# SAME51_PINOUT.net
KiCad netlist of a schematic drawn in Altium Designer
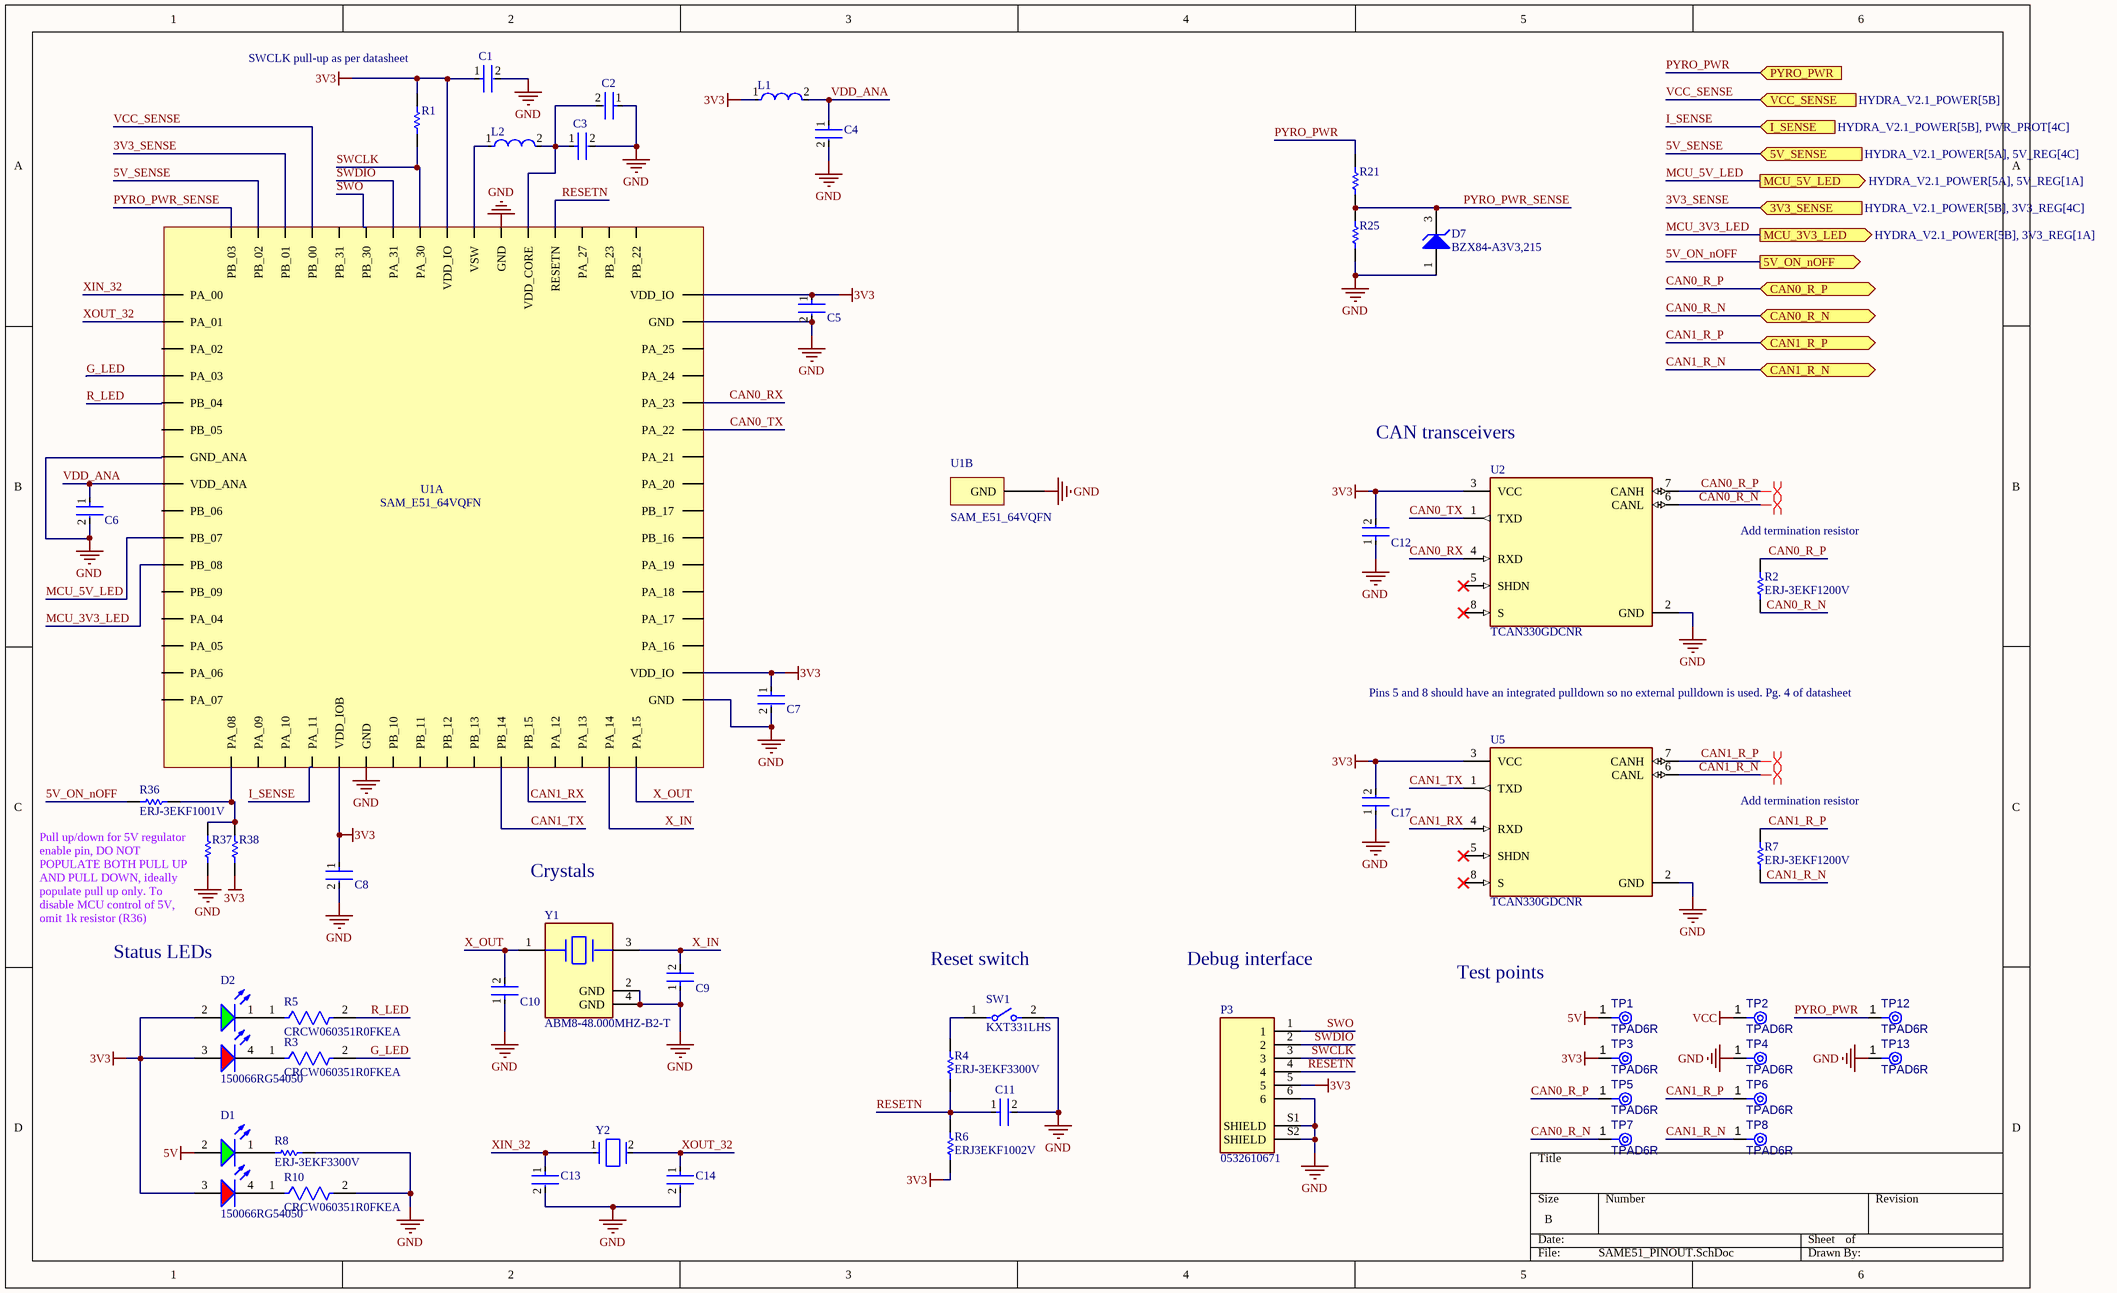
[diagram p0: SAME51_PINOUT.SchDoc]

(export (version "E")
  (design (tool "Eeschema 10.0.6"))
  (components
    (comp (ref "C1")
      (value "C0402C104K8PACTU")
      (footprint "FP-C0402-BB-MFG")
      (description "CAP CER 0.1UF 10V X5R 0402")
      (fields (field (name "MANUFACTURER") "Kemet") (field (name "TOLERANCE") "0.1"))
      (libsource (lib "Altium Content Vault") (part "b4654b650e69147ec39a6b967a45e02"))
    )
    (comp (ref "C2")
      (value "GRM155R60J475ME47D")
      (footprint "FP-GRM155-0_1-IPC_B")
      (description "Chip Multilayer Ceramic Capacitors for General Purpose, 0402, 4.7uF, X5R, 15%, 20%, 6.3V")
      (fields (field (name "VOLTAGE") "6.3V") (field (name "TOLERANCE") "20%"))
      (libsource (lib "Altium Content Vault") (part "11868f565c42a9108669ba33697ecf6"))
    )
    (comp (ref "C3")
      (value "C0402C104K8PACTU")
      (footprint "FP-C0402-BB-MFG")
      (description "CAP CER 0.1UF 10V X5R 0402")
      (fields (field (name "MANUFACTURER") "Kemet") (field (name "TOLERANCE") "0.1"))
      (libsource (lib "Altium Content Vault") (part "b4654b650e69147ec39a6b967a45e02"))
    )
    (comp (ref "C4")
      (value "C0805C106K8PACTU")
      (footprint "FP-C0805C-DG-MFG")
      (description "CAP CER 10UF 10V X5R 0805")
      (fields (field (name "TOLERANCE") "10%") (field (name "MANUFACTURER") "Kemet"))
      (libsource (lib "Altium Content Vault") (part "11868f565c42a9108669ba33697ecf6"))
    )
    (comp (ref "C5")
      (value "C0402C104K8PACTU")
      (footprint "FP-C0402-BB-MFG")
      (description "CAP CER 0.1UF 10V X5R 0402")
      (fields (field (name "MANUFACTURER") "Kemet") (field (name "TOLERANCE") "0.1"))
      (libsource (lib "Altium Content Vault") (part "b4654b650e69147ec39a6b967a45e02"))
    )
    (comp (ref "C6")
      (value "C0402C104K8PACTU")
      (footprint "FP-C0402-BB-MFG")
      (description "CAP CER 0.1UF 10V X5R 0402")
      (fields (field (name "MANUFACTURER") "Kemet") (field (name "TOLERANCE") "0.1"))
      (libsource (lib "Altium Content Vault") (part "b4654b650e69147ec39a6b967a45e02"))
    )
    (comp (ref "C7")
      (value "C0402C104K8PACTU")
      (footprint "FP-C0402-BB-MFG")
      (description "CAP CER 0.1UF 10V X5R 0402")
      (fields (field (name "MANUFACTURER") "Kemet") (field (name "TOLERANCE") "0.1"))
      (libsource (lib "Altium Content Vault") (part "b4654b650e69147ec39a6b967a45e02"))
    )
    (comp (ref "C8")
      (value "C0402C104K8PACTU")
      (footprint "FP-C0402-BB-MFG")
      (description "CAP CER 0.1UF 10V X5R 0402")
      (fields (field (name "MANUFACTURER") "Kemet") (field (name "TOLERANCE") "0.1"))
      (libsource (lib "Altium Content Vault") (part "b4654b650e69147ec39a6b967a45e02"))
    )
    (comp (ref "C9")
      (value "08051A6R8CAT2A")
      (footprint "FP-0805-L_2_01_0_2-W_1_25-MFG")
      (description "General Purpose Ceramic Capacitor, 0805, 6.8pF, 0.25pF, C0G, 30ppm/°C, 100V")
      (fields (field (name "VOLTAGE") "100V") (field (name "TOLERANCE") "5%"))
      (libsource (lib "Altium Content Vault") (part "02cd4be3c70576c341d710602a673aa"))
    )
    (comp (ref "C10")
      (value "08051A6R8CAT2A")
      (footprint "FP-0805-L_2_01_0_2-W_1_25-MFG")
      (description "General Purpose Ceramic Capacitor, 0805, 6.8pF, 0.25pF, C0G, 30ppm/°C, 100V")
      (fields (field (name "VOLTAGE") "100V") (field (name "TOLERANCE") "5%"))
      (libsource (lib "Altium Content Vault") (part "02cd4be3c70576c341d710602a673aa"))
    )
    (comp (ref "C11")
      (value "C0402C104K8PACTU")
      (footprint "FP-C0402-BB-MFG")
      (description "CAP CER 0.1UF 10V X5R 0402")
      (fields (field (name "MANUFACTURER") "Kemet") (field (name "TOLERANCE") "0.1"))
      (libsource (lib "Altium Content Vault") (part "b4654b650e69147ec39a6b967a45e02"))
    )
    (comp (ref "C12")
      (value "C0402C104K8PACTU")
      (footprint "FP-C0402-BB-MFG")
      (description "CAP CER 0.1UF 10V X5R 0402")
      (fields (field (name "MANUFACTURER") "Kemet") (field (name "TOLERANCE") "0.1"))
      (libsource (lib "Altium Content Vault") (part "b4654b650e69147ec39a6b967a45e02"))
    )
    (comp (ref "C13")
      (value "C0805C180J5GACTU")
      (footprint "FP-C0805C-DN-MFG")
      (description "CAP CER 18PF 50V C0G/NP0 0805")
      (fields
        (field (name "OCTOPART") "https://octopart.com/c0805c180j5gactu-kemet-144810")
        (field (name "TOLERANCE") "0.05")
      )
      (libsource (lib "Altium Content Vault") (part "b4654b650e69147ec39a6b967a45e02"))
    )
    (comp (ref "C14")
      (value "C0805C180J5GACTU")
      (footprint "FP-C0805C-DN-MFG")
      (description "CAP CER 18PF 50V C0G/NP0 0805")
      (fields
        (field (name "OCTOPART") "https://octopart.com/c0805c180j5gactu-kemet-144810")
        (field (name "TOLERANCE") "0.05")
      )
      (libsource (lib "Altium Content Vault") (part "b4654b650e69147ec39a6b967a45e02"))
    )
    (comp (ref "C17")
      (value "C0402C104K8PACTU")
      (footprint "FP-C0402-BB-MFG")
      (description "CAP CER 0.1UF 10V X5R 0402")
      (fields (field (name "MANUFACTURER") "Kemet") (field (name "TOLERANCE") "0.1"))
      (libsource (lib "Altium Content Vault") (part "b4654b650e69147ec39a6b967a45e02"))
    )
    (comp (ref "D1")
      (value "150066RG54050")
      (footprint "WL-SBCD_0606")
      (description "Led, Red/Grn, 180Mcd/230Mcd, 624Nm/525Nm Rohs Compliant: Yes")
      (libsource (lib "uORocketry Hardware") (part "WL-SBCD_0606_Red & Green"))
    )
    (comp (ref "D2")
      (value "150066RG54050")
      (footprint "WL-SBCD_0606")
      (description "Led, Red/Grn, 180Mcd/230Mcd, 624Nm/525Nm Rohs Compliant: Yes")
      (libsource (lib "uORocketry Hardware") (part "WL-SBCD_0606_Red & Green"))
    )
    (comp (ref "D7")
      (value "BZX84-A3V3,215")
      (footprint "SOT95P230X110-3N")
      (description "DIODE ZENER 3.3V 250MW SOT23")
      (libsource (lib "uORocketry Hardware") (part "BZX84-A3V3,215"))
    )
    (comp (ref "L1")
      (value "NR6028T100M")
      (footprint "FP-NR6028-MFG")
      (description "SMD Power Inductors 10uH ±20% 1.9A 84.5mΩ")
      (fields (field (name "TOLERANCE") "20%"))
      (libsource (lib "Altium Content Vault") (part "725321dda6339637d4d059423bc1c3c"))
    )
    (comp (ref "L2")
      (value "NR6028T100M")
      (footprint "FP-NR6028-MFG")
      (description "SMD Power Inductors 10uH ±20% 1.9A 84.5mΩ")
      (fields (field (name "TOLERANCE") "20%"))
      (libsource (lib "Altium Content Vault") (part "725321dda6339637d4d059423bc1c3c"))
    )
    (comp (ref "P3")
      (value "0532610671")
      (footprint "0532610671-Footprint-1")
      (description "Conn Shrouded Header (4 Sides) HDR 6 POS 1.25mm Solder RA Side Entry SMD PicoBlade™ T/R")
      (libsource (lib "uORocketry Hardware") (part "0532610671"))
    )
    (comp (ref "R1")
      (value "ERJ3EKF1002V")
      (footprint "RESC1609X55X30LL15T15")
      (description "Chip Resistor, 10 KOhm, +/- 1%, 0.1 W, -55 to 155 degC, 0603 (1608 Metric), RoHS, Tape and Reel")
      (fields (field (name "TOLERANCE") "1%") (field (name "MANUFACTURER") "Panasonic"))
      (libsource (lib "Altium Content Vault") (part "RES-2"))
    )
    (comp (ref "R2")
      (value "ERJ-3EKF1200V")
      (footprint "RESC1609X55X30ML15T15")
      (description "Chip Resistor, 120 Ohm, +/- 1%, 0.1 W, -55 to 155 degC, 0603 (1608 Metric), RoHS, Tape and Reel")
      (fields (field (name "TOLERANCE") "1%") (field (name "MANUFACTURER") "Panasonic"))
      (libsource (lib "Altium Content Vault") (part "RES-2"))
    )
    (comp (ref "R3")
      (value "CRCW060351R0FKEA")
      (footprint "FP-CRCW0603-e3-MFG")
      (description "RES Thick Film, 51Ω, 1%, 0.1W, 100ppm/°C, 0603")
      (fields (field (name "TOLERANCE") "1%"))
      (libsource (lib "Altium Content Vault") (part "1029c3af85768c4190bb7ad29bc67b5"))
    )
    (comp (ref "R4")
      (value "ERJ-3EKF3300V")
      (footprint "RESC1608X55X30LL15T15")
      (description "Chip Resistor, 330 Ohm, +/- 1%, 0.1 W, -55 to 155 degC, 0603 (1608 Metric), RoHS, Tape and Reel")
      (libsource (lib "Altium Content Vault") (part "RES-2"))
    )
    (comp (ref "R5")
      (value "CRCW060351R0FKEA")
      (footprint "FP-CRCW0603-e3-MFG")
      (description "RES Thick Film, 51Ω, 1%, 0.1W, 100ppm/°C, 0603")
      (fields (field (name "TOLERANCE") "1%"))
      (libsource (lib "Altium Content Vault") (part "1029c3af85768c4190bb7ad29bc67b5"))
    )
    (comp (ref "R6")
      (value "ERJ3EKF1002V")
      (footprint "RESC1609X55X30LL15T15")
      (description "Chip Resistor, 10 KOhm, +/- 1%, 0.1 W, -55 to 155 degC, 0603 (1608 Metric), RoHS, Tape and Reel")
      (fields (field (name "TOLERANCE") "1%") (field (name "MANUFACTURER") "Panasonic"))
      (libsource (lib "Altium Content Vault") (part "RES-2"))
    )
    (comp (ref "R7")
      (value "ERJ-3EKF1200V")
      (footprint "RESC1609X55X30ML15T15")
      (description "Chip Resistor, 120 Ohm, +/- 1%, 0.1 W, -55 to 155 degC, 0603 (1608 Metric), RoHS, Tape and Reel")
      (fields (field (name "TOLERANCE") "1%") (field (name "MANUFACTURER") "Panasonic"))
      (libsource (lib "Altium Content Vault") (part "RES-2"))
    )
    (comp (ref "R8")
      (value "ERJ-3EKF3300V")
      (footprint "RESC1608X55X30LL15T15")
      (description "Chip Resistor, 330 Ohm, +/- 1%, 0.1 W, -55 to 155 degC, 0603 (1608 Metric), RoHS, Tape and Reel")
      (libsource (lib "Altium Content Vault") (part "RES-2"))
    )
    (comp (ref "R10")
      (value "CRCW060351R0FKEA")
      (footprint "FP-CRCW0603-e3-MFG")
      (description "RES Thick Film, 51Ω, 1%, 0.1W, 100ppm/°C, 0603")
      (fields (field (name "TOLERANCE") "1%"))
      (libsource (lib "Altium Content Vault") (part "1029c3af85768c4190bb7ad29bc67b5"))
    )
    (comp (ref "R21")
      (value "ERJ3EKF1002V")
      (footprint "RESC1609X55X30LL15T15")
      (description "Chip Resistor, 10 KOhm, +/- 1%, 0.1 W, -55 to 155 degC, 0603 (1608 Metric), RoHS, Tape and Reel")
      (fields (field (name "TOLERANCE") "1%") (field (name "MANUFACTURER") "Panasonic"))
      (libsource (lib "Altium Content Vault") (part "RES-2"))
    )
    (comp (ref "R25")
      (value "CRCW06032K70JNEA")
      (footprint "RESC1609X50X30ML10T20")
      (fields (field (name "MANUFACTURER") "Vishay Dale"))
      (libsource (lib "Altium Content Vault") (part "RES"))
    )
    (comp (ref "R36")
      (value "ERJ-3EKF1001V")
      (footprint "RESC1608X55X30LL15T15")
      (fields (field (name "MANUFACTURER") "Panasonic"))
      (libsource (lib "Altium Content Vault") (part "RES"))
    )
    (comp (ref "R37")
      (value "ERJ3EKF1002V")
      (footprint "RESC1609X55X30LL15T15")
      (description "Chip Resistor, 10 KOhm, +/- 1%, 0.1 W, -55 to 155 degC, 0603 (1608 Metric), RoHS, Tape and Reel")
      (fields (field (name "TOLERANCE") "1%") (field (name "MANUFACTURER") "Panasonic"))
      (libsource (lib "Altium Content Vault") (part "RES-2"))
    )
    (comp (ref "R38")
      (value "ERJ3EKF1002V")
      (footprint "RESC1609X55X30LL15T15")
      (description "Chip Resistor, 10 KOhm, +/- 1%, 0.1 W, -55 to 155 degC, 0603 (1608 Metric), RoHS, Tape and Reel")
      (fields (field (name "TOLERANCE") "1%") (field (name "MANUFACTURER") "Panasonic"))
      (libsource (lib "Altium Content Vault") (part "RES-2"))
    )
    (comp (ref "SW1")
      (value "KXT331LHS")
      (footprint "FP-KXT331LHS-MFG")
      (description "SWITCH TACTILE SPST-NO 0.02A 15V")
      (libsource (lib "Altium Content Vault") (part "bb27bde45df87f1f469753f287ef5ae"))
    )
    (comp (ref "TP1")
      (value "TPAD6R")
      (footprint "TP06R")
      (description "0.6mm round")
      (libsource (lib "uORocketry Hardware") (part "CMP-001-0001-4"))
    )
    (comp (ref "TP2")
      (value "TPAD6R")
      (footprint "TP06R")
      (description "0.6mm round")
      (libsource (lib "uORocketry Hardware") (part "CMP-001-0001-4"))
    )
    (comp (ref "TP3")
      (value "TPAD6R")
      (footprint "TP06R")
      (description "0.6mm round")
      (libsource (lib "uORocketry Hardware") (part "CMP-001-0001-4"))
    )
    (comp (ref "TP4")
      (value "TPAD6R")
      (footprint "TP06R")
      (description "0.6mm round")
      (libsource (lib "uORocketry Hardware") (part "CMP-001-0001-4"))
    )
    (comp (ref "TP5")
      (value "TPAD6R")
      (footprint "TP06R")
      (description "0.6mm round")
      (libsource (lib "uORocketry Hardware") (part "CMP-001-0001-4"))
    )
    (comp (ref "TP6")
      (value "TPAD6R")
      (footprint "TP06R")
      (description "0.6mm round")
      (libsource (lib "uORocketry Hardware") (part "CMP-001-0001-4"))
    )
    (comp (ref "TP7")
      (value "TPAD6R")
      (footprint "TP06R")
      (description "0.6mm round")
      (libsource (lib "uORocketry Hardware") (part "CMP-001-0001-4"))
    )
    (comp (ref "TP8")
      (value "TPAD6R")
      (footprint "TP06R")
      (description "0.6mm round")
      (libsource (lib "uORocketry Hardware") (part "CMP-001-0001-4"))
    )
    (comp (ref "TP12")
      (value "TPAD6R")
      (footprint "TP06R")
      (description "0.6mm round")
      (libsource (lib "uORocketry Hardware") (part "CMP-001-0001-4"))
    )
    (comp (ref "TP13")
      (value "TPAD6R")
      (footprint "TP06R")
      (description "0.6mm round")
      (libsource (lib "uORocketry Hardware") (part "CMP-001-0001-4"))
    )
    (comp (ref "U1")
      (value "SAM_E51_64VQFN")
      (footprint "SAM_E51_64VQFN-Footprint-1")
      (description "Rudimentary symbol and footprint for the SAM E51 microcontroller")
      (libsource (lib "uORocketry Hardware") (part "SAM_E51_64VQFN-Symbol-1"))
    )
    (comp (ref "U2")
      (value "TCAN330GDCNR")
      (footprint "FP-DCN0008A-MFG")
      (description "IC TRANSCEIVER 1/1 SOT23-8")
      (libsource (lib "Altium Content Vault") (part "22681b49c22ad38c6a4e12e04c36c7a"))
    )
    (comp (ref "U5")
      (value "TCAN330GDCNR")
      (footprint "FP-DCN0008A-MFG")
      (description "IC TRANSCEIVER 1/1 SOT23-8")
      (libsource (lib "Altium Content Vault") (part "22681b49c22ad38c6a4e12e04c36c7a"))
    )
    (comp (ref "Y1")
      (value "ABM8-48.000MHZ-B2-T")
      (footprint "FP-ABM8-MFG")
      (description "Crystal 48MHz ±20ppm 18pF SMD-4 3.2mm x 2.5mm")
      (fields (field (name "TOLERANCE") "20ppm"))
      (libsource (lib "Altium Content Vault") (part "dfdb7f9a12507849fb681da9a70121c"))
    )
    (comp (ref "Y2")
      (value "ECS-.327-12.5-1210-TR")
      (footprint "FP-ECX-1210-MFG")
      (description "CRYSTAL 32.7680KHZ 12.5PF SMD")
      (fields
        (field (name "OCTOPART") "https://octopart.com/ecs-.327-12.5-1210-tr-ecs+international-81221340")
        (field (name "TOLERANCE") "20ppm")
      )
      (libsource (lib "Altium Content Vault") (part "99724985039315a44fd0d1401b84e49"))
    )
  )
  (nets
    (net (code "1") (name "/3V3_SENSE") (class "Default")
      (node (ref "U1") (pin "62") (pinfunction "PB_01_62") (pintype "passive"))
    )
    (net (code "2") (name "/5V_ON_nOFF") (class "Default")
      (node (ref "R36") (pin "1") (pinfunction "1_1") (pintype "passive"))
    )
    (net (code "3") (name "/5V_SENSE") (class "Default")
      (node (ref "U1") (pin "63") (pinfunction "PB_02_63") (pintype "passive"))
    )
    (net (code "4") (name "/CAN0_RX") (class "Default")
      (node (ref "U1") (pin "44") (pinfunction "PA_23_44") (pintype "passive"))
      (node (ref "U2") (pin "4") (pinfunction "RXD_4") (pintype "input"))
    )
    (net (code "5") (name "/CAN0_R_N") (class "Default")
      (node (ref "R2") (pin "1") (pinfunction "1_1") (pintype "passive"))
      (node (ref "TP7") (pin "1") (pinfunction "TP_1") (pintype "passive"))
      (node (ref "U2") (pin "6") (pinfunction "CANL_6") (pintype "bidirectional"))
    )
    (net (code "6") (name "/CAN0_R_P") (class "Default")
      (node (ref "R2") (pin "2") (pinfunction "2_2") (pintype "passive"))
      (node (ref "TP5") (pin "1") (pinfunction "TP_1") (pintype "passive"))
      (node (ref "U2") (pin "7") (pinfunction "CANH_7") (pintype "bidirectional"))
    )
    (net (code "7") (name "/CAN0_TX") (class "Default")
      (node (ref "U1") (pin "43") (pinfunction "PA_22_43") (pintype "passive"))
      (node (ref "U2") (pin "1") (pinfunction "TXD_1") (pintype "output"))
    )
    (net (code "8") (name "/CAN1_RX") (class "Default")
      (node (ref "U1") (pin "28") (pinfunction "PB_15_28") (pintype "passive"))
      (node (ref "U5") (pin "4") (pinfunction "RXD_4") (pintype "input"))
    )
    (net (code "9") (name "/CAN1_R_N") (class "Default")
      (node (ref "R7") (pin "1") (pinfunction "1_1") (pintype "passive"))
      (node (ref "TP8") (pin "1") (pinfunction "TP_1") (pintype "passive"))
      (node (ref "U5") (pin "6") (pinfunction "CANL_6") (pintype "bidirectional"))
    )
    (net (code "10") (name "/CAN1_R_P") (class "Default")
      (node (ref "R7") (pin "2") (pinfunction "2_2") (pintype "passive"))
      (node (ref "TP6") (pin "1") (pinfunction "TP_1") (pintype "passive"))
      (node (ref "U5") (pin "7") (pinfunction "CANH_7") (pintype "bidirectional"))
    )
    (net (code "11") (name "/CAN1_TX") (class "Default")
      (node (ref "U1") (pin "27") (pinfunction "PB_14_27") (pintype "passive"))
      (node (ref "U5") (pin "1") (pinfunction "TXD_1") (pintype "output"))
    )
    (net (code "12") (name "/G_LED") (class "Default")
      (node (ref "R3") (pin "2") (pinfunction "2_2") (pintype "passive"))
      (node (ref "U1") (pin "4") (pinfunction "PA_03_4") (pintype "passive"))
    )
    (net (code "13") (name "/I_SENSE") (class "Default")
      (node (ref "U1") (pin "20") (pinfunction "PA_11_20") (pintype "passive"))
    )
    (net (code "14") (name "/MCU_3V3_LED") (class "Default")
      (node (ref "U1") (pin "11") (pinfunction "PB_08_11") (pintype "passive"))
    )
    (net (code "15") (name "/MCU_5V_LED") (class "Default")
      (node (ref "U1") (pin "10") (pinfunction "PB_07_10") (pintype "passive"))
    )
    (net (code "16") (name "/PYRO_PWR") (class "Default")
      (node (ref "R21") (pin "2") (pinfunction "2_2") (pintype "passive"))
      (node (ref "TP12") (pin "1") (pinfunction "TP_1") (pintype "passive"))
    )
    (net (code "17") (name "/PYRO_PWR_SENSE") (class "Default")
      (node (ref "D7") (pin "3") (pinfunction "K_3") (pintype "passive"))
      (node (ref "R21") (pin "1") (pinfunction "1_1") (pintype "passive"))
      (node (ref "R25") (pin "2") (pinfunction "2_2") (pintype "passive"))
      (node (ref "U1") (pin "64") (pinfunction "PB_03_64") (pintype "passive"))
    )
    (net (code "18") (name "/RESETN") (class "Default")
      (node (ref "C11") (pin "1") (pinfunction "1_1") (pintype "passive"))
      (node (ref "P3") (pin "4") (pinfunction "4_4") (pintype "passive"))
      (node (ref "R4") (pin "1") (pinfunction "1_1") (pintype "passive"))
      (node (ref "R6") (pin "2") (pinfunction "2_2") (pintype "passive"))
      (node (ref "U1") (pin "52") (pinfunction "RESETN_52") (pintype "passive"))
    )
    (net (code "19") (name "/R_LED") (class "Default")
      (node (ref "R5") (pin "2") (pinfunction "2_2") (pintype "passive"))
      (node (ref "U1") (pin "5") (pinfunction "PB_04_5") (pintype "passive"))
    )
    (net (code "20") (name "/SWCLK") (class "Default")
      (node (ref "P3") (pin "3") (pinfunction "3_3") (pintype "passive"))
      (node (ref "R1") (pin "1") (pinfunction "1_1") (pintype "passive"))
      (node (ref "U1") (pin "57") (pinfunction "PA_30_57") (pintype "passive"))
    )
    (net (code "21") (name "/SWDIO") (class "Default")
      (node (ref "P3") (pin "2") (pinfunction "2_2") (pintype "passive"))
      (node (ref "U1") (pin "58") (pinfunction "PA_31_58") (pintype "passive"))
    )
    (net (code "22") (name "/SWO") (class "Default")
      (node (ref "P3") (pin "1") (pinfunction "1_1") (pintype "passive"))
      (node (ref "U1") (pin "59") (pinfunction "PB_30_59") (pintype "passive"))
    )
    (net (code "23") (name "/VCC_SENSE") (class "Default")
      (node (ref "U1") (pin "61") (pinfunction "PB_00_61") (pintype "passive"))
    )
    (net (code "24") (name "/VDD_ANA") (class "Default")
      (node (ref "C4") (pin "1") (pinfunction "1_1") (pintype "passive"))
      (node (ref "C6") (pin "1") (pinfunction "1_1") (pintype "passive"))
      (node (ref "L1") (pin "2") (pinfunction "2_2") (pintype "passive"))
      (node (ref "U1") (pin "8") (pinfunction "VDD_ANA_8") (pintype "passive"))
    )
    (net (code "25") (name "/XIN_32") (class "Default")
      (node (ref "C13") (pin "1") (pinfunction "1_1") (pintype "passive"))
      (node (ref "U1") (pin "1") (pinfunction "PA_00_1") (pintype "passive"))
      (node (ref "Y2") (pin "1") (pinfunction "In/Out_1") (pintype "passive"))
    )
    (net (code "26") (name "/XOUT_32") (class "Default")
      (node (ref "C14") (pin "1") (pinfunction "1_1") (pintype "passive"))
      (node (ref "U1") (pin "2") (pinfunction "PA_01_2") (pintype "passive"))
      (node (ref "Y2") (pin "2") (pinfunction "Out/In_2") (pintype "passive"))
    )
    (net (code "27") (name "/X_IN") (class "Default")
      (node (ref "C9") (pin "2") (pinfunction "2_2") (pintype "passive"))
      (node (ref "U1") (pin "31") (pinfunction "PA_14_31") (pintype "passive"))
      (node (ref "Y1") (pin "3") (pinfunction "3_3") (pintype "passive"))
    )
    (net (code "28") (name "/X_OUT") (class "Default")
      (node (ref "C10") (pin "2") (pinfunction "2_2") (pintype "passive"))
      (node (ref "U1") (pin "32") (pinfunction "PA_15_32") (pintype "passive"))
      (node (ref "Y1") (pin "1") (pinfunction "1_1") (pintype "passive"))
    )
    (net (code "29") (name "3V3") (class "Default")
      (node (ref "C1") (pin "1") (pinfunction "1_1") (pintype "passive"))
      (node (ref "C12") (pin "2") (pinfunction "2_2") (pintype "passive"))
      (node (ref "C17") (pin "2") (pinfunction "2_2") (pintype "passive"))
      (node (ref "C5") (pin "1") (pinfunction "1_1") (pintype "passive"))
      (node (ref "C7") (pin "1") (pinfunction "1_1") (pintype "passive"))
      (node (ref "C8") (pin "1") (pinfunction "1_1") (pintype "passive"))
      (node (ref "D1") (pin "3") (pinfunction "A_3") (pintype "passive"))
      (node (ref "D2") (pin "2") (pinfunction "A_2") (pintype "passive"))
      (node (ref "D2") (pin "3") (pinfunction "A_3") (pintype "passive"))
      (node (ref "L1") (pin "1") (pinfunction "1_1") (pintype "passive"))
      (node (ref "P3") (pin "5") (pinfunction "5_5") (pintype "passive"))
      (node (ref "R1") (pin "2") (pinfunction "2_2") (pintype "passive"))
      (node (ref "R38") (pin "1") (pinfunction "1_1") (pintype "passive"))
      (node (ref "R6") (pin "1") (pinfunction "1_1") (pintype "passive"))
      (node (ref "TP3") (pin "1") (pinfunction "TP_1") (pintype "passive"))
      (node (ref "U1") (pin "21") (pinfunction "VDD_IOB_21") (pintype "passive"))
      (node (ref "U1") (pin "34") (pinfunction "VDD_IO_34") (pintype "passive"))
      (node (ref "U1") (pin "48") (pinfunction "VDD_IO_48") (pintype "passive"))
      (node (ref "U1") (pin "56") (pinfunction "VDD_IO_56") (pintype "passive"))
      (node (ref "U2") (pin "3") (pinfunction "VCC_3") (pintype "power_in"))
      (node (ref "U5") (pin "3") (pinfunction "VCC_3") (pintype "power_in"))
    )
    (net (code "30") (name "5V") (class "Default")
      (node (ref "D1") (pin "2") (pinfunction "A_2") (pintype "passive"))
      (node (ref "TP1") (pin "1") (pinfunction "TP_1") (pintype "passive"))
    )
    (net (code "31") (name "GND") (class "Default")
      (node (ref "C1") (pin "2") (pinfunction "2_2") (pintype "passive"))
      (node (ref "C10") (pin "1") (pinfunction "1_1") (pintype "passive"))
      (node (ref "C11") (pin "2") (pinfunction "2_2") (pintype "passive"))
      (node (ref "C12") (pin "1") (pinfunction "1_1") (pintype "passive"))
      (node (ref "C13") (pin "2") (pinfunction "2_2") (pintype "passive"))
      (node (ref "C14") (pin "2") (pinfunction "2_2") (pintype "passive"))
      (node (ref "C17") (pin "1") (pinfunction "1_1") (pintype "passive"))
      (node (ref "C2") (pin "1") (pinfunction "1_1") (pintype "passive"))
      (node (ref "C3") (pin "2") (pinfunction "2_2") (pintype "passive"))
      (node (ref "C4") (pin "2") (pinfunction "2_2") (pintype "passive"))
      (node (ref "C5") (pin "2") (pinfunction "2_2") (pintype "passive"))
      (node (ref "C6") (pin "2") (pinfunction "2_2") (pintype "passive"))
      (node (ref "C7") (pin "2") (pinfunction "2_2") (pintype "passive"))
      (node (ref "C8") (pin "2") (pinfunction "2_2") (pintype "passive"))
      (node (ref "C9") (pin "1") (pinfunction "1_1") (pintype "passive"))
      (node (ref "D7") (pin "1") (pinfunction "A_1") (pintype "passive"))
      (node (ref "P3") (pin "6") (pinfunction "6_6") (pintype "passive"))
      (node (ref "P3") (pin "S1") (pinfunction "SHIELD_S1") (pintype "passive"))
      (node (ref "P3") (pin "S2") (pinfunction "SHIELD_S2") (pintype "passive"))
      (node (ref "R10") (pin "2") (pinfunction "2_2") (pintype "passive"))
      (node (ref "R25") (pin "1") (pinfunction "1_1") (pintype "passive"))
      (node (ref "R37") (pin "1") (pinfunction "1_1") (pintype "passive"))
      (node (ref "R8") (pin "2") (pinfunction "2_2") (pintype "passive"))
      (node (ref "SW1") (pin "2") (pinfunction "2_2") (pintype "passive"))
      (node (ref "TP13") (pin "1") (pinfunction "TP_1") (pintype "passive"))
      (node (ref "TP4") (pin "1") (pinfunction "TP_1") (pintype "passive"))
      (node (ref "U1") (pin "22") (pinfunction "GND_22") (pintype "passive"))
      (node (ref "U1") (pin "33") (pinfunction "GND_33") (pintype "passive"))
      (node (ref "U1") (pin "47") (pinfunction "GND_47") (pintype "passive"))
      (node (ref "U1") (pin "54") (pinfunction "GND_54") (pintype "passive"))
      (node (ref "U1") (pin "65") (pinfunction "GND_65") (pintype "passive"))
      (node (ref "U1") (pin "7") (pinfunction "GND_ANA_7") (pintype "passive"))
      (node (ref "U2") (pin "2") (pinfunction "GND_2") (pintype "power_in"))
      (node (ref "U5") (pin "2") (pinfunction "GND_2") (pintype "power_in"))
      (node (ref "Y1") (pin "2") (pinfunction "GND_2") (pintype "power_in"))
      (node (ref "Y1") (pin "4") (pinfunction "GND_4") (pintype "power_in"))
    )
    (net (code "32") (name "Net-(D1-K-Pad1)") (class "Default")
      (node (ref "D1") (pin "1") (pinfunction "K_1") (pintype "passive"))
      (node (ref "R8") (pin "1") (pinfunction "1_1") (pintype "passive"))
    )
    (net (code "33") (name "Net-(D1-K-Pad4)") (class "Default")
      (node (ref "D1") (pin "4") (pinfunction "K_4") (pintype "passive"))
      (node (ref "R10") (pin "1") (pinfunction "1_1") (pintype "passive"))
    )
    (net (code "34") (name "Net-(D2-K-Pad1)") (class "Default")
      (node (ref "D2") (pin "1") (pinfunction "K_1") (pintype "passive"))
      (node (ref "R5") (pin "1") (pinfunction "1_1") (pintype "passive"))
    )
    (net (code "35") (name "Net-(D2-K-Pad4)") (class "Default")
      (node (ref "D2") (pin "4") (pinfunction "K_4") (pintype "passive"))
      (node (ref "R3") (pin "1") (pinfunction "1_1") (pintype "passive"))
    )
    (net (code "36") (name "Net-(R4-Pad2)") (class "Default")
      (node (ref "R4") (pin "2") (pinfunction "2_2") (pintype "passive"))
      (node (ref "SW1") (pin "1") (pinfunction "1_1") (pintype "passive"))
    )
    (net (code "37") (name "Net-(U1A-PA_08)") (class "Default")
      (node (ref "R36") (pin "2") (pinfunction "2_2") (pintype "passive"))
      (node (ref "R37") (pin "2") (pinfunction "2_2") (pintype "passive"))
      (node (ref "R38") (pin "2") (pinfunction "2_2") (pintype "passive"))
      (node (ref "U1") (pin "17") (pinfunction "PA_08_17") (pintype "passive"))
    )
    (net (code "38") (name "Net-(U1A-VDD_CORE)") (class "Default")
      (node (ref "C2") (pin "2") (pinfunction "2_2") (pintype "passive"))
      (node (ref "C3") (pin "1") (pinfunction "1_1") (pintype "passive"))
      (node (ref "L2") (pin "2") (pinfunction "2_2") (pintype "passive"))
      (node (ref "U1") (pin "53") (pinfunction "VDD_CORE_53") (pintype "passive"))
    )
    (net (code "39") (name "Net-(U1A-VSW)") (class "Default")
      (node (ref "L2") (pin "1") (pinfunction "1_1") (pintype "passive"))
      (node (ref "U1") (pin "55") (pinfunction "VSW_55") (pintype "passive"))
    )
    (net (code "40") (name "VCC") (class "Default")
      (node (ref "TP2") (pin "1") (pinfunction "TP_1") (pintype "passive"))
    )
    (net (code "41") (name "unconnected-(U1A-PA_02-Pad3)") (class "Default")
      (node (ref "U1") (pin "3") (pinfunction "PA_02_3") (pintype "passive"))
    )
    (net (code "42") (name "unconnected-(U1A-PA_04-Pad13)") (class "Default")
      (node (ref "U1") (pin "13") (pinfunction "PA_04_13") (pintype "passive"))
    )
    (net (code "43") (name "unconnected-(U1A-PA_05-Pad14)") (class "Default")
      (node (ref "U1") (pin "14") (pinfunction "PA_05_14") (pintype "passive"))
    )
    (net (code "44") (name "unconnected-(U1A-PA_06-Pad15)") (class "Default")
      (node (ref "U1") (pin "15") (pinfunction "PA_06_15") (pintype "passive"))
    )
    (net (code "45") (name "unconnected-(U1A-PA_07-Pad16)") (class "Default")
      (node (ref "U1") (pin "16") (pinfunction "PA_07_16") (pintype "passive"))
    )
    (net (code "46") (name "unconnected-(U1A-PA_09-Pad18)") (class "Default")
      (node (ref "U1") (pin "18") (pinfunction "PA_09_18") (pintype "passive"))
    )
    (net (code "47") (name "unconnected-(U1A-PA_10-Pad19)") (class "Default")
      (node (ref "U1") (pin "19") (pinfunction "PA_10_19") (pintype "passive"))
    )
    (net (code "48") (name "unconnected-(U1A-PA_12-Pad29)") (class "Default")
      (node (ref "U1") (pin "29") (pinfunction "PA_12_29") (pintype "passive"))
    )
    (net (code "49") (name "unconnected-(U1A-PA_13-Pad30)") (class "Default")
      (node (ref "U1") (pin "30") (pinfunction "PA_13_30") (pintype "passive"))
    )
    (net (code "50") (name "unconnected-(U1A-PA_16-Pad35)") (class "Default")
      (node (ref "U1") (pin "35") (pinfunction "PA_16_35") (pintype "passive"))
    )
    (net (code "51") (name "unconnected-(U1A-PA_17-Pad36)") (class "Default")
      (node (ref "U1") (pin "36") (pinfunction "PA_17_36") (pintype "passive"))
    )
    (net (code "52") (name "unconnected-(U1A-PA_18-Pad37)") (class "Default")
      (node (ref "U1") (pin "37") (pinfunction "PA_18_37") (pintype "passive"))
    )
    (net (code "53") (name "unconnected-(U1A-PA_19-Pad38)") (class "Default")
      (node (ref "U1") (pin "38") (pinfunction "PA_19_38") (pintype "passive"))
    )
    (net (code "54") (name "unconnected-(U1A-PA_20-Pad41)") (class "Default")
      (node (ref "U1") (pin "41") (pinfunction "PA_20_41") (pintype "passive"))
    )
    (net (code "55") (name "unconnected-(U1A-PA_21-Pad42)") (class "Default")
      (node (ref "U1") (pin "42") (pinfunction "PA_21_42") (pintype "passive"))
    )
    (net (code "56") (name "unconnected-(U1A-PA_24-Pad45)") (class "Default")
      (node (ref "U1") (pin "45") (pinfunction "PA_24_45") (pintype "passive"))
    )
    (net (code "57") (name "unconnected-(U1A-PA_25-Pad46)") (class "Default")
      (node (ref "U1") (pin "46") (pinfunction "PA_25_46") (pintype "passive"))
    )
    (net (code "58") (name "unconnected-(U1A-PA_27-Pad51)") (class "Default")
      (node (ref "U1") (pin "51") (pinfunction "PA_27_51") (pintype "passive"))
    )
    (net (code "59") (name "unconnected-(U1A-PB_05-Pad6)") (class "Default")
      (node (ref "U1") (pin "6") (pinfunction "PB_05_6") (pintype "passive"))
    )
    (net (code "60") (name "unconnected-(U1A-PB_06-Pad9)") (class "Default")
      (node (ref "U1") (pin "9") (pinfunction "PB_06_9") (pintype "passive"))
    )
    (net (code "61") (name "unconnected-(U1A-PB_09-Pad12)") (class "Default")
      (node (ref "U1") (pin "12") (pinfunction "PB_09_12") (pintype "passive"))
    )
    (net (code "62") (name "unconnected-(U1A-PB_10-Pad23)") (class "Default")
      (node (ref "U1") (pin "23") (pinfunction "PB_10_23") (pintype "passive"))
    )
    (net (code "63") (name "unconnected-(U1A-PB_11-Pad24)") (class "Default")
      (node (ref "U1") (pin "24") (pinfunction "PB_11_24") (pintype "passive"))
    )
    (net (code "64") (name "unconnected-(U1A-PB_12-Pad25)") (class "Default")
      (node (ref "U1") (pin "25") (pinfunction "PB_12_25") (pintype "passive"))
    )
    (net (code "65") (name "unconnected-(U1A-PB_13-Pad26)") (class "Default")
      (node (ref "U1") (pin "26") (pinfunction "PB_13_26") (pintype "passive"))
    )
    (net (code "66") (name "unconnected-(U1A-PB_16-Pad39)") (class "Default")
      (node (ref "U1") (pin "39") (pinfunction "PB_16_39") (pintype "passive"))
    )
    (net (code "67") (name "unconnected-(U1A-PB_17-Pad40)") (class "Default")
      (node (ref "U1") (pin "40") (pinfunction "PB_17_40") (pintype "passive"))
    )
    (net (code "68") (name "unconnected-(U1A-PB_22-Pad49)") (class "Default")
      (node (ref "U1") (pin "49") (pinfunction "PB_22_49") (pintype "passive"))
    )
    (net (code "69") (name "unconnected-(U1A-PB_23-Pad50)") (class "Default")
      (node (ref "U1") (pin "50") (pinfunction "PB_23_50") (pintype "passive"))
    )
    (net (code "70") (name "unconnected-(U1A-PB_31-Pad60)") (class "Default")
      (node (ref "U1") (pin "60") (pinfunction "PB_31_60") (pintype "passive"))
    )
    (net (code "71") (name "unconnected-(U2-S-Pad8)") (class "Default")
      (node (ref "U2") (pin "8") (pinfunction "S_8") (pintype "input+no_connect"))
    )
    (net (code "72") (name "unconnected-(U2-SHDN-Pad5)") (class "Default")
      (node (ref "U2") (pin "5") (pinfunction "SHDN_5") (pintype "input+no_connect"))
    )
    (net (code "73") (name "unconnected-(U5-S-Pad8)") (class "Default")
      (node (ref "U5") (pin "8") (pinfunction "S_8") (pintype "input+no_connect"))
    )
    (net (code "74") (name "unconnected-(U5-SHDN-Pad5)") (class "Default")
      (node (ref "U5") (pin "5") (pinfunction "SHDN_5") (pintype "input+no_connect"))
    )
  )
)
